# ZHSD-RS485-CAN.net
KiCad netlist of a schematic drawn in Altium Designer
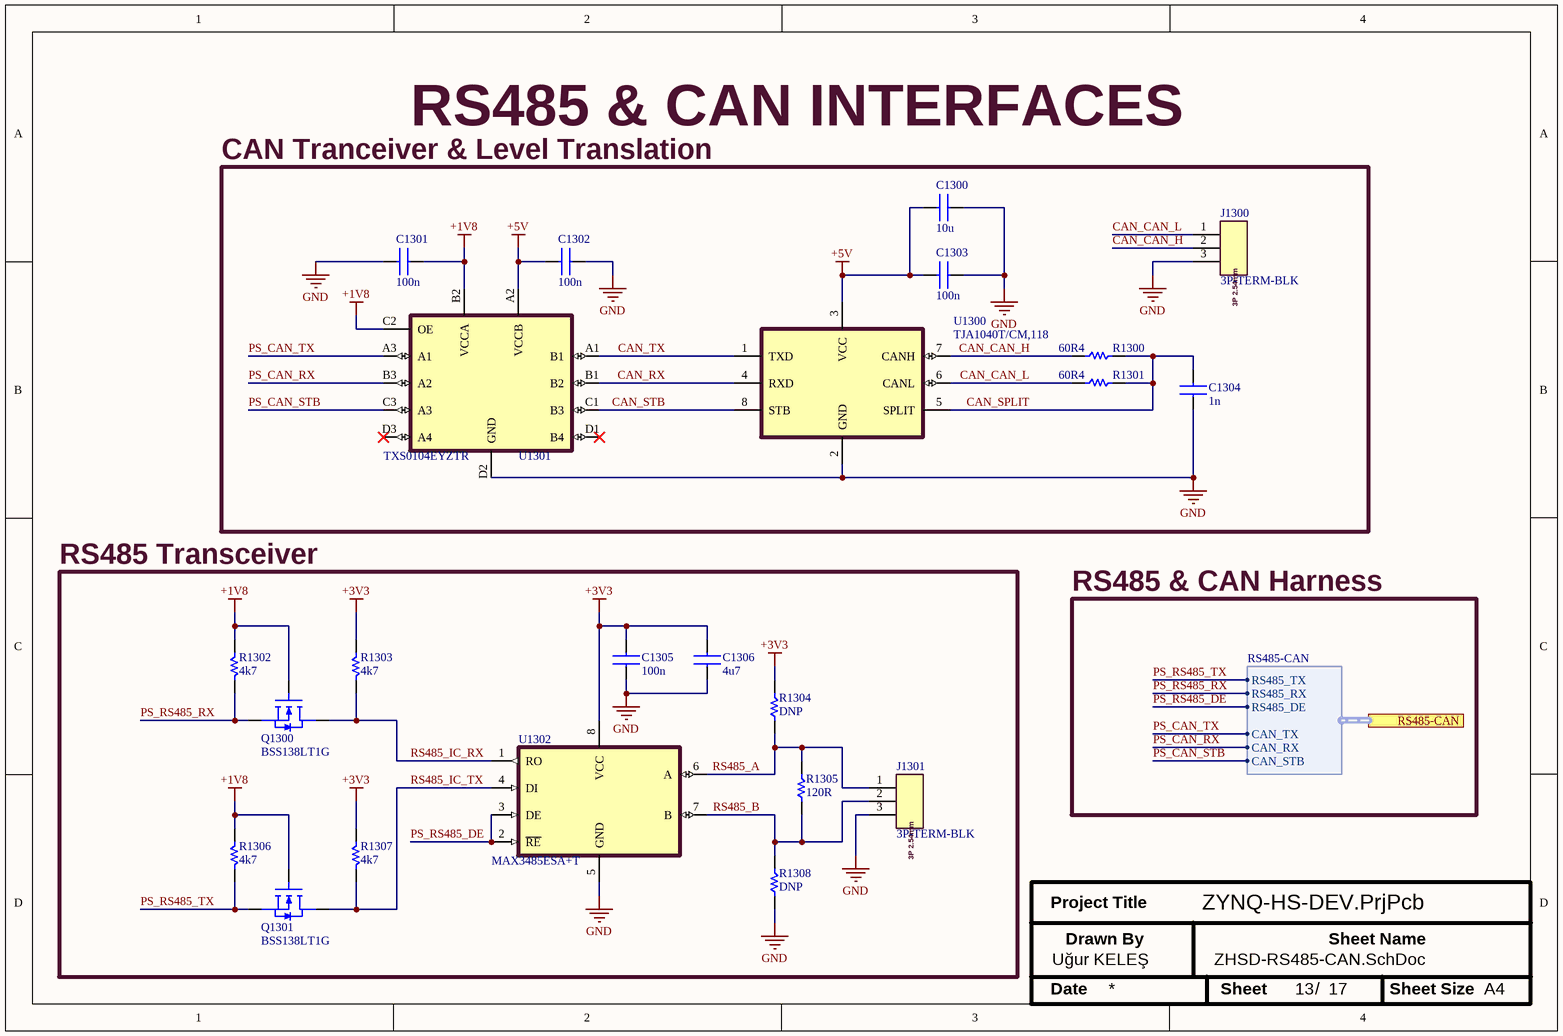
[diagram p0: ZHSD-RS485-CAN.SchDoc]

(export (version "E")
  (design (tool "Eeschema 10.0.6"))
  (components
    (comp (ref "C1300")
      (value "10u")
      (footprint "0603CAPC1608X09N")
      (description "CAP CER 10UF 10V X7R 0603 (1608) ±20%")
      (fields (field (name "MANUFACTURER") "Murata Electronics") (field (name "MPN") "GRM188Z71A106MA73D"))
      (libsource (lib "UK_Library") (part "GRM188Z71A106MA73D"))
    )
    (comp (ref "C1301")
      (value "100n")
      (footprint "0603CAPC1608X09N")
      (description "CAP CER 0.1UF 16V X7R 0402 (1005) ±10%")
      (fields (field (name "MANUFACTURER") "Murata Electronics") (field (name "MPN") "GRM155R71C104KA88J"))
      (libsource (lib "UK_Library") (part "GRM155R71C104KA88J"))
    )
    (comp (ref "C1302")
      (value "100n")
      (footprint "0603CAPC1608X09N")
      (description "CAP CER 0.1UF 16V X7R 0402 (1005) ±10%")
      (fields (field (name "MANUFACTURER") "Murata Electronics") (field (name "MPN") "GRM155R71C104KA88J"))
      (libsource (lib "UK_Library") (part "GRM155R71C104KA88J"))
    )
    (comp (ref "C1303")
      (value "100n")
      (footprint "0603CAPC1608X09N")
      (description "CAP CER 0.1UF 16V X7R 0402 (1005) ±10%")
      (fields (field (name "MANUFACTURER") "Murata Electronics") (field (name "MPN") "GRM155R71C104KA88J"))
      (libsource (lib "UK_Library") (part "GRM155R71C104KA88J"))
    )
    (comp (ref "C1304")
      (value "1n")
      (footprint "0603CAPC1608X09N")
      (description "CAP CER 1000PF 50V X7R 0603 (1608) ±10%")
      (fields (field (name "MANUFACTURER") "Murata Electronics") (field (name "MPN") "GCM188R71H102KA37D"))
      (libsource (lib "UK_Library") (part "GCM188R71H102KA37D"))
    )
    (comp (ref "C1305")
      (value "100n")
      (footprint "0603CAPC1608X09N")
      (description "CAP CER 0.1UF 16V X7R 0402 (1005) ±10%")
      (fields (field (name "MANUFACTURER") "Murata Electronics") (field (name "MPN") "GRM155R71C104KA88J"))
      (libsource (lib "UK_Library") (part "GRM155R71C104KA88J"))
    )
    (comp (ref "C1306")
      (value "4u7")
      (footprint "0603CAPC1608X09N")
      (description "CAP CER 4.7UF 10V X5R 0603 (1608) ±10%")
      (fields
        (field (name "MANUFACTURER") "Samsung Electro-Mechanics")
        (field (name "MPN") "CL10A475KP8NNNC")
      )
      (libsource (lib "UK_Library") (part "CL10A475KP8NNNC"))
    )
    (comp (ref "J1300")
      (value "3P-TERM-BLK")
      (footprint "CONN-3P-TERM-BLK")
      (description "TERM BLK 3P SIDE ENT 2.54MM PCB")
      (libsource (lib "UK_Library") (part "282834-3"))
    )
    (comp (ref "J1301")
      (value "3P-TERM-BLK")
      (footprint "CONN-3P-TERM-BLK")
      (description "TERM BLK 3P SIDE ENT 2.54MM PCB")
      (libsource (lib "UK_Library") (part "282834-3"))
    )
    (comp (ref "Q1300")
      (value "BSS138LT1G")
      (footprint "SOT95P237X89-3N")
      (description "N-Channel 50 V 200mA (Ta) 225mW (Ta) Surface Mount SOT-23-3 (TO-236)")
      (fields (field (name "MANUFACTURER") "onsemi"))
      (libsource (lib "UK_Library") (part "BSS138LT1G"))
    )
    (comp (ref "Q1301")
      (value "BSS138LT1G")
      (footprint "SOT95P237X89-3N")
      (description "N-Channel 50 V 200mA (Ta) 225mW (Ta) Surface Mount SOT-23-3 (TO-236)")
      (fields (field (name "MANUFACTURER") "onsemi"))
      (libsource (lib "UK_Library") (part "BSS138LT1G"))
    )
    (comp (ref "R1300")
      (value "60R4")
      (footprint "0402RESC1005X04N")
      (description "RES 60.4 OHM 1% 1/16W 0402 (1005)")
      (fields (field (name "MANUFACTURER") "YAGEO") (field (name "MPN") "RC0402FR-0760R4L"))
      (libsource (lib "UK_Library") (part "RC0402FR-0760R4L"))
    )
    (comp (ref "R1301")
      (value "60R4")
      (footprint "0402RESC1005X04N")
      (description "RES 60.4 OHM 1% 1/16W 0402 (1005)")
      (fields (field (name "MANUFACTURER") "YAGEO") (field (name "MPN") "RC0402FR-0760R4L"))
      (libsource (lib "UK_Library") (part "RC0402FR-0760R4L"))
    )
    (comp (ref "R1302")
      (value "4k7")
      (footprint "0402RESC1005X04N")
      (description "RES 4.7K OHM 5% 1/16W 0402 (1005)")
      (fields (field (name "MANUFACTURER") "YAGEO") (field (name "MPN") "RT0402FRE0780RL"))
      (libsource (lib "UK_Library") (part "RC0402JR-074K7L"))
    )
    (comp (ref "R1303")
      (value "4k7")
      (footprint "0402RESC1005X04N")
      (description "RES 4.7K OHM 5% 1/16W 0402 (1005)")
      (fields (field (name "MANUFACTURER") "YAGEO") (field (name "MPN") "RT0402FRE0780RL"))
      (libsource (lib "UK_Library") (part "RC0402JR-074K7L"))
    )
    (comp (ref "R1304")
      (value "DNP")
      (footprint "0402RESC1005X04N")
      (description "DO NOT POPULATE RESISTOR")
      (fields (field (name "MANUFACTURER") "***"))
      (libsource (lib "UK_Library") (part "DNP_RES"))
    )
    (comp (ref "R1305")
      (value "120R")
      (footprint "0402RESC1005X04N")
      (description "RES 120 OHM 1% 1/16W 0402 (1005)")
      (fields (field (name "MANUFACTURER") "YAGEO") (field (name "MPN") "RC0402FR-07120RL"))
      (libsource (lib "UK_Library") (part "RC0402FR-07120RL"))
    )
    (comp (ref "R1306")
      (value "4k7")
      (footprint "0402RESC1005X04N")
      (description "RES 4.7K OHM 5% 1/16W 0402 (1005)")
      (fields (field (name "MANUFACTURER") "YAGEO") (field (name "MPN") "RT0402FRE0780RL"))
      (libsource (lib "UK_Library") (part "RC0402JR-074K7L"))
    )
    (comp (ref "R1307")
      (value "4k7")
      (footprint "0402RESC1005X04N")
      (description "RES 4.7K OHM 5% 1/16W 0402 (1005)")
      (fields (field (name "MANUFACTURER") "YAGEO") (field (name "MPN") "RT0402FRE0780RL"))
      (libsource (lib "UK_Library") (part "RC0402JR-074K7L"))
    )
    (comp (ref "R1308")
      (value "DNP")
      (footprint "0402RESC1005X04N")
      (description "DO NOT POPULATE RESISTOR")
      (fields (field (name "MANUFACTURER") "***"))
      (libsource (lib "UK_Library") (part "DNP_RES"))
    )
    (comp (ref "U1300")
      (value "TJA1040T/CM,118")
      (footprint "SOIC127P600X175-8N")
      (description "CAN Interface IC High-Speed CAN Transceiver with Standby Mode SOIC8")
      (fields (field (name "MANUFACTURER") "NXP USA Inc."))
      (libsource (lib "UK_Library") (part "TJA1040T/CM,118"))
    )
    (comp (ref "U1301")
      (value "TXS0104EYZTR")
      (footprint "BGA12C50P3X4")
      (description "Voltage Level Translator Bidirectional 1 Circuit 4 Channel 24Mbps 12-DSBGA (1.9x1.4)")
      (fields (field (name "MANUFACTURER") "Texas Instruments"))
      (libsource (lib "UK_Library") (part "TXS0104EYZTR"))
    )
    (comp (ref "U1302")
      (value "MAX3485ESA+T")
      (footprint "SOIC127P600X175-8N")
      (description "1/1 Transceiver Half RS422, RS485 8-SOIC")
      (fields (field (name "MANUFACTURER") "Analog Devices Inc./Maxim Integrated"))
      (libsource (lib "UK_Library") (part "MAX3485ESA+T"))
    )
  )
  (nets
    (net (code "2") (name "+1V8") (class "Default")
      (node (ref "C1301") (pin "2") (pinfunction "2_2") (pintype "passive"))
      (node (ref "Q1300") (pin "1") (pinfunction "G_1") (pintype "passive"))
      (node (ref "Q1301") (pin "1") (pinfunction "G_1") (pintype "passive"))
      (node (ref "R1302") (pin "1") (pinfunction "1_1") (pintype "passive"))
      (node (ref "R1306") (pin "1") (pinfunction "1_1") (pintype "passive"))
      (node (ref "U1301") (pin "B2") (pinfunction "VCCA_B2") (pintype "power_in"))
      (node (ref "U1301") (pin "C2") (pinfunction "OE_C2") (pintype "passive"))
    )
    (net (code "3") (name "+3V3") (class "Default")
      (node (ref "C1305") (pin "2") (pinfunction "2_2") (pintype "passive"))
      (node (ref "C1306") (pin "2") (pinfunction "2_2") (pintype "passive"))
      (node (ref "R1303") (pin "1") (pinfunction "1_1") (pintype "passive"))
      (node (ref "R1304") (pin "2") (pinfunction "2_2") (pintype "passive"))
      (node (ref "R1307") (pin "1") (pinfunction "1_1") (pintype "passive"))
      (node (ref "U1302") (pin "8") (pinfunction "VCC_8") (pintype "power_in"))
    )
    (net (code "4") (name "+5V") (class "Default")
      (node (ref "C1300") (pin "2") (pinfunction "2_2") (pintype "passive"))
      (node (ref "C1302") (pin "2") (pinfunction "2_2") (pintype "passive"))
      (node (ref "C1303") (pin "2") (pinfunction "2_2") (pintype "passive"))
      (node (ref "U1300") (pin "3") (pinfunction "VCC_3") (pintype "power_in"))
      (node (ref "U1301") (pin "A2") (pinfunction "VCCB_A2") (pintype "power_in"))
    )
    (net (code "5") (name "/CAN_CAN_H") (class "Default")
      (node (ref "J1300") (pin "2") (pinfunction "2_2") (pintype "passive"))
      (node (ref "R1300") (pin "1") (pinfunction "1_1") (pintype "passive"))
      (node (ref "U1300") (pin "7") (pinfunction "CANH_7") (pintype "bidirectional"))
    )
    (net (code "6") (name "/CAN_CAN_L") (class "Default")
      (node (ref "J1300") (pin "1") (pinfunction "1_1") (pintype "passive"))
      (node (ref "R1301") (pin "1") (pinfunction "1_1") (pintype "passive"))
      (node (ref "U1300") (pin "6") (pinfunction "CANL_6") (pintype "bidirectional"))
    )
    (net (code "7") (name "/CAN_RX") (class "Default")
      (node (ref "U1300") (pin "4") (pinfunction "RXD_4") (pintype "passive"))
      (node (ref "U1301") (pin "B1") (pinfunction "B2_B1") (pintype "bidirectional"))
    )
    (net (code "8") (name "/CAN_SPLIT") (class "Default")
      (node (ref "C1304") (pin "2") (pinfunction "2_2") (pintype "passive"))
      (node (ref "R1300") (pin "2") (pinfunction "2_2") (pintype "passive"))
      (node (ref "R1301") (pin "2") (pinfunction "2_2") (pintype "passive"))
      (node (ref "U1300") (pin "5") (pinfunction "SPLIT_5") (pintype "passive"))
    )
    (net (code "9") (name "/CAN_STB") (class "Default")
      (node (ref "U1300") (pin "8") (pinfunction "STB_8") (pintype "passive"))
      (node (ref "U1301") (pin "C1") (pinfunction "B3_C1") (pintype "bidirectional"))
    )
    (net (code "10") (name "/CAN_TX") (class "Default")
      (node (ref "U1300") (pin "1") (pinfunction "TXD_1") (pintype "passive"))
      (node (ref "U1301") (pin "A1") (pinfunction "B1_A1") (pintype "bidirectional"))
    )
    (net (code "11") (name "/PS_CAN_RX") (class "Default")
      (node (ref "U1301") (pin "B3") (pinfunction "A2_B3") (pintype "bidirectional"))
    )
    (net (code "12") (name "/PS_CAN_STB") (class "Default")
      (node (ref "U1301") (pin "C3") (pinfunction "A3_C3") (pintype "bidirectional"))
    )
    (net (code "13") (name "/PS_CAN_TX") (class "Default")
      (node (ref "U1301") (pin "A3") (pinfunction "A1_A3") (pintype "bidirectional"))
    )
    (net (code "14") (name "/PS_RS485_DE") (class "Default")
      (node (ref "U1302") (pin "2") (pinfunction "RE_2") (pintype "input"))
      (node (ref "U1302") (pin "3") (pinfunction "DE_3") (pintype "input"))
    )
    (net (code "15") (name "/PS_RS485_RX") (class "Default")
      (node (ref "Q1300") (pin "2") (pinfunction "S_2") (pintype "passive"))
      (node (ref "R1302") (pin "2") (pinfunction "2_2") (pintype "passive"))
    )
    (net (code "16") (name "/PS_RS485_TX") (class "Default")
      (node (ref "Q1301") (pin "2") (pinfunction "S_2") (pintype "passive"))
      (node (ref "R1306") (pin "2") (pinfunction "2_2") (pintype "passive"))
    )
    (net (code "17") (name "/RS485_A") (class "Default")
      (node (ref "J1301") (pin "1") (pinfunction "1_1") (pintype "passive"))
      (node (ref "R1304") (pin "1") (pinfunction "1_1") (pintype "passive"))
      (node (ref "R1305") (pin "2") (pinfunction "2_2") (pintype "passive"))
      (node (ref "U1302") (pin "6") (pinfunction "A_6") (pintype "bidirectional"))
    )
    (net (code "18") (name "/RS485_B") (class "Default")
      (node (ref "J1301") (pin "2") (pinfunction "2_2") (pintype "passive"))
      (node (ref "R1305") (pin "1") (pinfunction "1_1") (pintype "passive"))
      (node (ref "R1308") (pin "2") (pinfunction "2_2") (pintype "passive"))
      (node (ref "U1302") (pin "7") (pinfunction "B_7") (pintype "bidirectional"))
    )
    (net (code "19") (name "/RS485_IC_RX") (class "Default")
      (node (ref "Q1300") (pin "3") (pinfunction "D_3") (pintype "passive"))
      (node (ref "R1303") (pin "2") (pinfunction "2_2") (pintype "passive"))
      (node (ref "U1302") (pin "1") (pinfunction "RO_1") (pintype "output"))
    )
    (net (code "20") (name "/RS485_IC_TX") (class "Default")
      (node (ref "Q1301") (pin "3") (pinfunction "D_3") (pintype "passive"))
      (node (ref "R1307") (pin "2") (pinfunction "2_2") (pintype "passive"))
      (node (ref "U1302") (pin "4") (pinfunction "DI_4") (pintype "input"))
    )
    (net (code "22") (name "GND") (class "Default")
      (node (ref "C1300") (pin "1") (pinfunction "1_1") (pintype "passive"))
      (node (ref "C1301") (pin "1") (pinfunction "1_1") (pintype "passive"))
      (node (ref "C1302") (pin "1") (pinfunction "1_1") (pintype "passive"))
      (node (ref "C1303") (pin "1") (pinfunction "1_1") (pintype "passive"))
      (node (ref "C1304") (pin "1") (pinfunction "1_1") (pintype "passive"))
      (node (ref "C1305") (pin "1") (pinfunction "1_1") (pintype "passive"))
      (node (ref "C1306") (pin "1") (pinfunction "1_1") (pintype "passive"))
      (node (ref "J1300") (pin "3") (pinfunction "3_3") (pintype "passive"))
      (node (ref "J1301") (pin "3") (pinfunction "3_3") (pintype "passive"))
      (node (ref "R1308") (pin "1") (pinfunction "1_1") (pintype "passive"))
      (node (ref "U1300") (pin "2") (pinfunction "GND_2") (pintype "power_in"))
      (node (ref "U1301") (pin "D2") (pinfunction "GND_D2") (pintype "power_in"))
      (node (ref "U1302") (pin "5") (pinfunction "GND_5") (pintype "power_in"))
    )
    (net (code "23") (name "unconnected-(U1301-A4-PadD3)") (class "Default")
      (node (ref "U1301") (pin "D3") (pinfunction "A4_D3") (pintype "bidirectional+no_connect"))
    )
    (net (code "24") (name "unconnected-(U1301-B4-PadD1)") (class "Default")
      (node (ref "U1301") (pin "D1") (pinfunction "B4_D1") (pintype "bidirectional+no_connect"))
    )
  )
)
